# Storage.net
KiCad netlist of a schematic drawn in Altium Designer
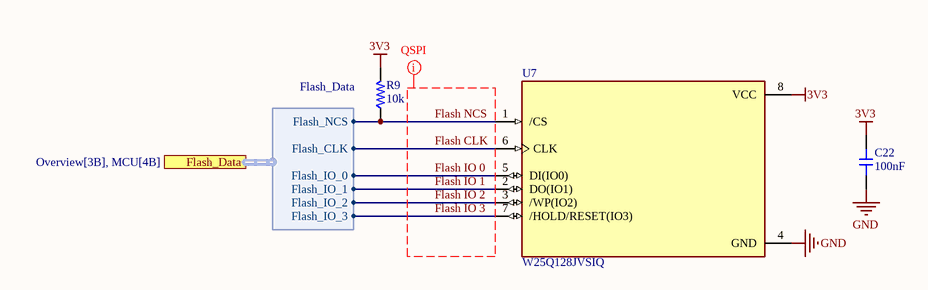
[diagram p0: Storage.SchDoc]

(export (version "E")
  (design (tool "Eeschema 10.0.6"))
  (components
    (comp (ref "C22")
      (value "100nF")
      (footprint "CAP-0402")
      (description "Capacitor, Ceramic (MLCC), 100nF, ±10%, 16V, X7R, ±10%, SMD 0402")
      (fields (field (name "TOLERANCE") "10%") (field (name "JLCPCB BASIC PART") "Yes"))
      (libsource (lib "StrathSEDS") (part "GRM21BR61H106KE43L"))
    )
    (comp (ref "R9")
      (value "10k")
      (footprint "RES-0402")
      (description "Resistor, 10kΩ, ±1%, 62.5mW, 50V, ±100ppm/℃, -55℃~+155℃, SMD 0402")
      (fields (field (name "TOLERANCE") "1%") (field (name "JLCPCB PART NUMBER") "C25744"))
      (libsource (lib "StrathSEDS") (part "1206W4F7500T5E"))
    )
    (comp (ref "U7")
      (value "W25Q128JVSIQ")
      (footprint "SOIC127P790X216-8N")
      (description "FLASH - NOR Memory IC 128Mb (16M x 8) SPI - Quad I/O, QPI, DTR 133 MHz 8-SOIC")
      (fields (field (name "MF") "Winbond Electronics") (field (name "LCSC PART #") "C97521"))
      (libsource (lib "StrathSEDS") (part "W25Q128JVSIQ"))
    )
  )
  (nets
    (net (code "2") (name "/Flash CLK") (class "Default")
      (node (ref "U7") (pin "6") (pinfunction "CLK_6") (pintype "input"))
    )
    (net (code "3") (name "/Flash IO 0") (class "Default")
      (node (ref "U7") (pin "5") (pinfunction "DI(IO0)_5") (pintype "bidirectional"))
    )
    (net (code "4") (name "/Flash IO 1") (class "Default")
      (node (ref "U7") (pin "2") (pinfunction "DO(IO1)_2") (pintype "bidirectional"))
    )
    (net (code "5") (name "/Flash IO 2") (class "Default")
      (node (ref "U7") (pin "3") (pinfunction "/WP(IO2)_3") (pintype "bidirectional"))
    )
    (net (code "6") (name "/Flash IO 3") (class "Default")
      (node (ref "U7") (pin "7") (pinfunction "/HOLD/RESET(IO3)_7") (pintype "bidirectional"))
    )
    (net (code "7") (name "/Flash NCS") (class "Default")
      (node (ref "R9") (pin "1") (pinfunction "1_1") (pintype "passive"))
      (node (ref "U7") (pin "1") (pinfunction "/CS_1") (pintype "input"))
    )
    (net (code "9") (name "3V3") (class "Default")
      (node (ref "C22") (pin "2") (pinfunction "2_2") (pintype "passive"))
      (node (ref "R9") (pin "2") (pinfunction "2_2") (pintype "passive"))
      (node (ref "U7") (pin "8") (pinfunction "VCC_8") (pintype "power_in"))
    )
    (net (code "10") (name "GND") (class "Default")
      (node (ref "C22") (pin "1") (pinfunction "1_1") (pintype "passive"))
      (node (ref "U7") (pin "4") (pinfunction "GND_4") (pintype "power_in"))
    )
  )
)
